# STC89C52.net
KiCad netlist of a schematic drawn in Altium Designer
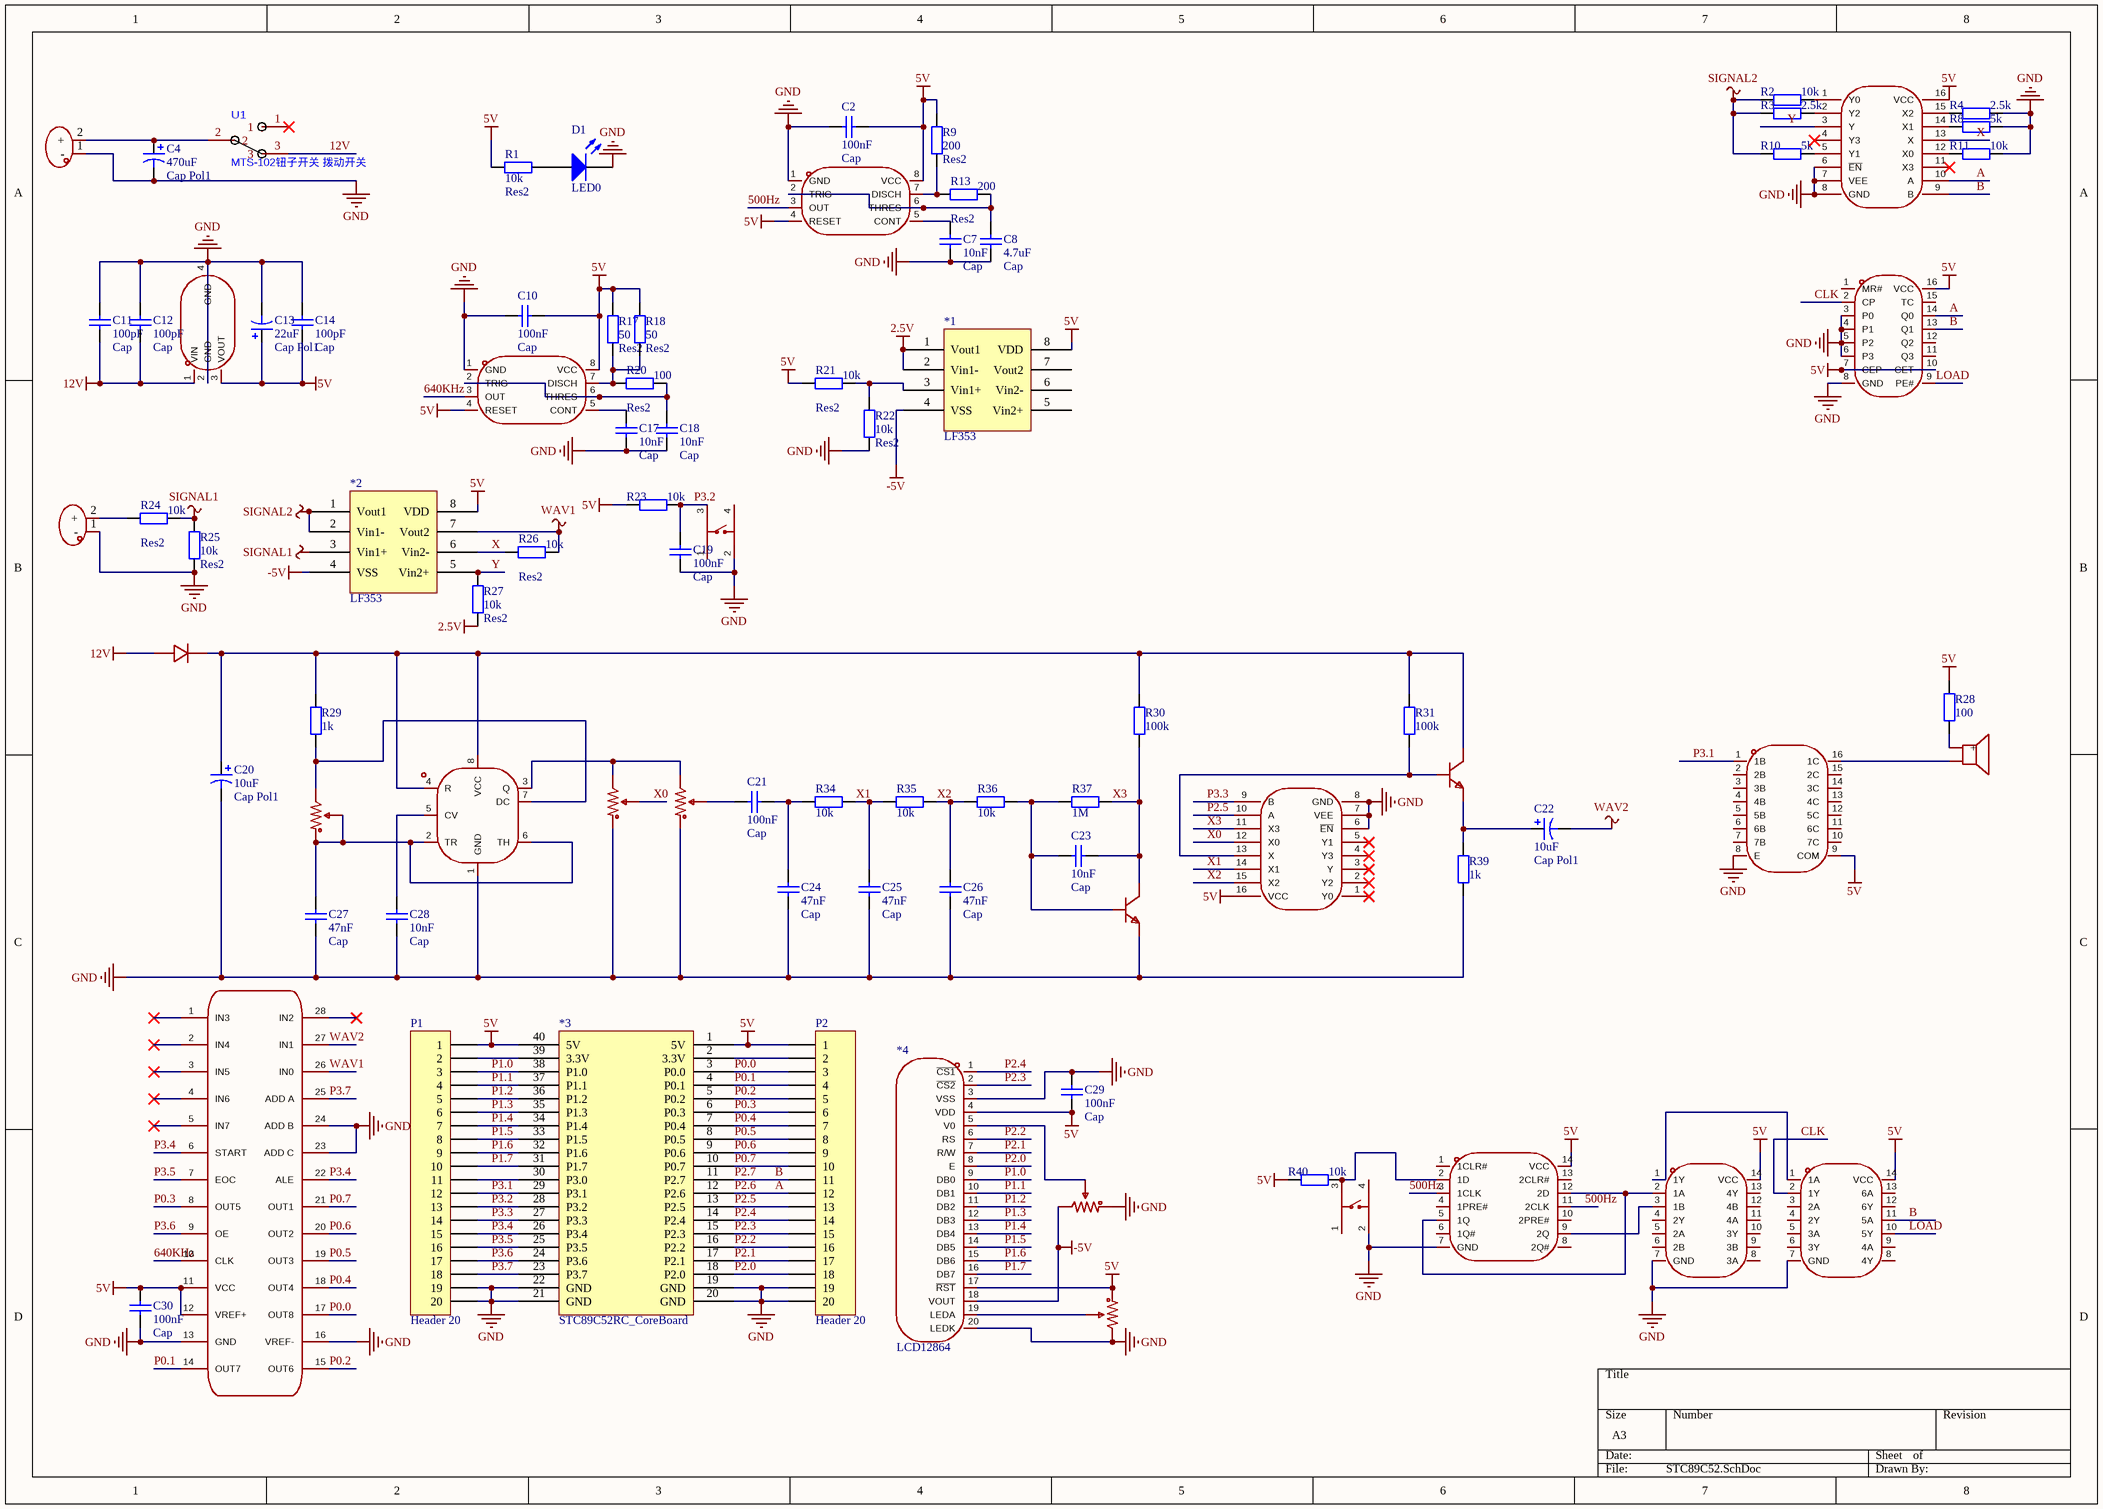
[diagram p0: STC89C52.SchDoc]

(export (version "E")
  (design (tool "Eeschema 10.0.6"))
  (components
    (comp (ref "*1") (value "LF353") (footprint "MCP6022") (libsource (lib "STC89C52") (part "MCP6022")))
    (comp (ref "*2") (value "LF353") (footprint "MCP6022") (libsource (lib "STC89C52") (part "MCP6022")))
    (comp (ref "*3")
      (value "STC89C52RC_CoreBoard")
      (footprint "STC89C52RC_CoreBoard")
      (libsource (lib "STC89C52") (part "STC89C52RC_CoreBoard"))
    )
    (comp (ref "*4") (value "LCD12864") (footprint "LCD12864") (libsource (lib "STC89C52") (part "LCD12864")))
    (comp (ref "BUZZER1")
      (value "2.7kHz")
      (footprint "BEEP 5x9x5.5")
      (fields (field (name "MANUFACTURER") "华能") (field (name "MANUFACTURER PART") "TMB12A05"))
      (libsource (lib "缩微光电核心板（CYT2BL3）") (part "蜂鸣器"))
    )
    (comp (ref "C2")
      (value "Cap")
      (footprint "C0603_M")
      (description "Capacitor")
      (fields (field (name "ALTIUM_VALUE") "100nF") (field (name "PUBLISHER") "Altium Limited"))
      (libsource (lib "Miscellaneous Devices") (part "Cap"))
    )
    (comp (ref "C4")
      (value "Cap Pol1")
      (footprint "CAP-SMD_BD8.0-L8.3-W8.3-FD")
      (description "Polarized Capacitor (Radial)")
      (fields (field (name "ALTIUM_VALUE") "470uF") (field (name "PUBLISHER") "Altium Limited"))
      (libsource (lib "Miscellaneous Devices") (part "Cap Pol1"))
    )
    (comp (ref "C7")
      (value "Cap")
      (footprint "C0603_M")
      (description "Capacitor")
      (fields (field (name "ALTIUM_VALUE") "10nF") (field (name "PUBLISHER") "Altium Limited"))
      (libsource (lib "Miscellaneous Devices") (part "Cap"))
    )
    (comp (ref "C8")
      (value "Cap")
      (footprint "C0603_M")
      (description "Capacitor")
      (fields (field (name "ALTIUM_VALUE") "4.7uF") (field (name "PUBLISHER") "Altium Limited"))
      (libsource (lib "Miscellaneous Devices") (part "Cap"))
    )
    (comp (ref "C10")
      (value "Cap")
      (footprint "C0603_M")
      (description "Capacitor")
      (fields (field (name "ALTIUM_VALUE") "100nF") (field (name "PUBLISHER") "Altium Limited"))
      (libsource (lib "Miscellaneous Devices") (part "Cap"))
    )
    (comp (ref "C11")
      (value "Cap")
      (footprint "C0603_M")
      (description "Capacitor")
      (fields (field (name "ALTIUM_VALUE") "100pF") (field (name "PUBLISHER") "Altium Limited"))
      (libsource (lib "Miscellaneous Devices") (part "Cap"))
    )
    (comp (ref "C12")
      (value "Cap")
      (footprint "C0603_M")
      (description "Capacitor")
      (fields (field (name "ALTIUM_VALUE") "100pF") (field (name "PUBLISHER") "Altium Limited"))
      (libsource (lib "Miscellaneous Devices") (part "Cap"))
    )
    (comp (ref "C13")
      (value "Cap Pol1")
      (footprint "C_3528")
      (description "Polarized Capacitor (Radial)")
      (fields (field (name "ALTIUM_VALUE") "22uF") (field (name "PUBLISHER") "Altium Limited"))
      (libsource (lib "Miscellaneous Devices") (part "Cap Pol1"))
    )
    (comp (ref "C14")
      (value "Cap")
      (footprint "C0603_M")
      (description "Capacitor")
      (fields (field (name "ALTIUM_VALUE") "100pF") (field (name "PUBLISHER") "Altium Limited"))
      (libsource (lib "Miscellaneous Devices") (part "Cap"))
    )
    (comp (ref "C17")
      (value "Cap")
      (footprint "C0603_M")
      (description "Capacitor")
      (fields (field (name "ALTIUM_VALUE") "10nF") (field (name "PUBLISHER") "Altium Limited"))
      (libsource (lib "Miscellaneous Devices") (part "Cap"))
    )
    (comp (ref "C18")
      (value "Cap")
      (footprint "C0603_M")
      (description "Capacitor")
      (fields (field (name "ALTIUM_VALUE") "10nF") (field (name "PUBLISHER") "Altium Limited"))
      (libsource (lib "Miscellaneous Devices") (part "Cap"))
    )
    (comp (ref "C19")
      (value "Cap")
      (footprint "C0603_M")
      (description "Capacitor")
      (fields (field (name "ALTIUM_VALUE") "100nF") (field (name "PUBLISHER") "Altium Limited"))
      (libsource (lib "Miscellaneous Devices") (part "Cap"))
    )
    (comp (ref "C20")
      (value "Cap Pol1")
      (footprint "C_3528")
      (description "Polarized Capacitor (Radial)")
      (fields (field (name "ALTIUM_VALUE") "10uF") (field (name "PUBLISHER") "Altium Limited"))
      (libsource (lib "Miscellaneous Devices") (part "Cap Pol1"))
    )
    (comp (ref "C21")
      (value "Cap")
      (footprint "C0603_M")
      (description "Capacitor")
      (fields (field (name "ALTIUM_VALUE") "100nF") (field (name "PUBLISHER") "Altium Limited"))
      (libsource (lib "Miscellaneous Devices") (part "Cap"))
    )
    (comp (ref "C22")
      (value "Cap Pol1")
      (footprint "C_3528")
      (description "Polarized Capacitor (Radial)")
      (fields (field (name "ALTIUM_VALUE") "10uF") (field (name "PUBLISHER") "Altium Limited"))
      (libsource (lib "Miscellaneous Devices") (part "Cap Pol1"))
    )
    (comp (ref "C23")
      (value "Cap")
      (footprint "C0603_M")
      (description "Capacitor")
      (fields (field (name "ALTIUM_VALUE") "10nF") (field (name "PUBLISHER") "Altium Limited"))
      (libsource (lib "Miscellaneous Devices") (part "Cap"))
    )
    (comp (ref "C24")
      (value "Cap")
      (footprint "C0603_M")
      (description "Capacitor")
      (fields (field (name "ALTIUM_VALUE") "47nF") (field (name "PUBLISHER") "Altium Limited"))
      (libsource (lib "Miscellaneous Devices") (part "Cap"))
    )
    (comp (ref "C25")
      (value "Cap")
      (footprint "C0603_M")
      (description "Capacitor")
      (fields (field (name "ALTIUM_VALUE") "47nF") (field (name "PUBLISHER") "Altium Limited"))
      (libsource (lib "Miscellaneous Devices") (part "Cap"))
    )
    (comp (ref "C26")
      (value "Cap")
      (footprint "C0603_M")
      (description "Capacitor")
      (fields (field (name "ALTIUM_VALUE") "47nF") (field (name "PUBLISHER") "Altium Limited"))
      (libsource (lib "Miscellaneous Devices") (part "Cap"))
    )
    (comp (ref "C27")
      (value "Cap")
      (footprint "C0603_M")
      (description "Capacitor")
      (fields (field (name "ALTIUM_VALUE") "47nF") (field (name "PUBLISHER") "Altium Limited"))
      (libsource (lib "Miscellaneous Devices") (part "Cap"))
    )
    (comp (ref "C28")
      (value "Cap")
      (footprint "C0603_M")
      (description "Capacitor")
      (fields (field (name "ALTIUM_VALUE") "10nF") (field (name "PUBLISHER") "Altium Limited"))
      (libsource (lib "Miscellaneous Devices") (part "Cap"))
    )
    (comp (ref "C29")
      (value "Cap")
      (footprint "C0603_M")
      (description "Capacitor")
      (fields (field (name "ALTIUM_VALUE") "100nF") (field (name "PUBLISHER") "Altium Limited"))
      (libsource (lib "Miscellaneous Devices") (part "Cap"))
    )
    (comp (ref "C30")
      (value "Cap")
      (footprint "C0603_M")
      (description "Capacitor")
      (fields (field (name "ALTIUM_VALUE") "100nF") (field (name "PUBLISHER") "Altium Limited"))
      (libsource (lib "Miscellaneous Devices") (part "Cap"))
    )
    (comp (ref "D1")
      (value "LED0")
      (footprint "LED0805_W")
      (description "Typical INFRARED GaAs LED")
      (fields (field (name "PUBLISHER") "Altium Limited"))
      (libsource (lib "Miscellaneous Devices") (part "LED0"))
    )
    (comp (ref "D4")
      (value "1N4007W_C18199088")
      (footprint "1N4007")
      (libsource (lib "STC89C52") (part "1N4007W_C18199088"))
    )
    (comp (ref "P1")
      (value "Header 20")
      (footprint "HDR1X20")
      (description "Header, 20-Pin")
      (fields (field (name "PUBLISHER") "Altium Limited"))
      (libsource (lib "Miscellaneous Connectors") (part "Header 20"))
    )
    (comp (ref "P2")
      (value "Header 20")
      (footprint "HDR1X20")
      (description "Header, 20-Pin")
      (fields (field (name "PUBLISHER") "Altium Limited"))
      (libsource (lib "") (part "Header 20_1"))
    )
    (comp (ref "Q3")
      (value "MMS8050-H-TP")
      (footprint "S8050")
      (libsource (lib "STC89C52") (part "MMS8050-H-TP"))
    )
    (comp (ref "Q4")
      (value "MMS8050-H-TP")
      (footprint "S8050")
      (libsource (lib "STC89C52") (part "MMS8050-H-TP"))
    )
    (comp (ref "R1")
      (value "Res2")
      (footprint "R0603_M")
      (description "Resistor")
      (fields (field (name "ALTIUM_VALUE") "10k") (field (name "PUBLISHER") "Altium Limited"))
      (libsource (lib "") (part "Res2_2"))
    )
    (comp (ref "R2")
      (value "10k")
      (footprint "R0603_M")
      (description "Resistor")
      (fields (field (name "Comment") "Res2") (field (name "PUBLISHER") "Altium Limited"))
      (libsource (lib "Miscellaneous Devices") (part "Res2"))
    )
    (comp (ref "R3")
      (value "2.5k")
      (footprint "R0603_M")
      (description "Resistor")
      (fields (field (name "Comment") "Res2") (field (name "PUBLISHER") "Altium Limited"))
      (libsource (lib "Miscellaneous Devices") (part "Res2"))
    )
    (comp (ref "R4")
      (value "2.5k")
      (footprint "R0603_M")
      (description "Resistor")
      (fields (field (name "Comment") "Res2") (field (name "PUBLISHER") "Altium Limited"))
      (libsource (lib "Miscellaneous Devices") (part "Res2"))
    )
    (comp (ref "R8")
      (value "5k")
      (footprint "R0603_M")
      (description "Resistor")
      (fields (field (name "Comment") "Res2") (field (name "PUBLISHER") "Altium Limited"))
      (libsource (lib "Miscellaneous Devices") (part "Res2"))
    )
    (comp (ref "R9")
      (value "Res2")
      (footprint "R0603_M")
      (description "Resistor")
      (fields (field (name "ALTIUM_VALUE") "200") (field (name "PUBLISHER") "Altium Limited"))
      (libsource (lib "") (part "Res2_3"))
    )
    (comp (ref "R10")
      (value "5k")
      (footprint "R0603_M")
      (description "Resistor")
      (fields (field (name "Comment") "Res2") (field (name "PUBLISHER") "Altium Limited"))
      (libsource (lib "Miscellaneous Devices") (part "Res2"))
    )
    (comp (ref "R11")
      (value "10k")
      (footprint "R0603_M")
      (description "Resistor")
      (fields (field (name "Comment") "Res2") (field (name "PUBLISHER") "Altium Limited"))
      (libsource (lib "Miscellaneous Devices") (part "Res2"))
    )
    (comp (ref "R13")
      (value "Res2")
      (footprint "R0603_M")
      (description "Resistor")
      (fields (field (name "ALTIUM_VALUE") "200") (field (name "PUBLISHER") "Altium Limited"))
      (libsource (lib "Miscellaneous Devices") (part "Res2"))
    )
    (comp (ref "R17")
      (value "Res2")
      (footprint "R0603_M")
      (description "Resistor")
      (fields (field (name "ALTIUM_VALUE") "50") (field (name "PUBLISHER") "Altium Limited"))
      (libsource (lib "") (part "Res2_3"))
    )
    (comp (ref "R18")
      (value "Res2")
      (footprint "R0603_M")
      (description "Resistor")
      (fields (field (name "ALTIUM_VALUE") "50") (field (name "PUBLISHER") "Altium Limited"))
      (libsource (lib "") (part "Res2_3"))
    )
    (comp (ref "R20")
      (value "Res2")
      (footprint "R0603_M")
      (description "Resistor")
      (fields (field (name "ALTIUM_VALUE") "100") (field (name "PUBLISHER") "Altium Limited"))
      (libsource (lib "Miscellaneous Devices") (part "Res2"))
    )
    (comp (ref "R21")
      (value "Res2")
      (footprint "R0603_M")
      (description "Resistor")
      (fields (field (name "ALTIUM_VALUE") "10k") (field (name "PUBLISHER") "Altium Limited"))
      (libsource (lib "Miscellaneous Devices") (part "Res2"))
    )
    (comp (ref "R22")
      (value "Res2")
      (footprint "R0603_M")
      (description "Resistor")
      (fields (field (name "ALTIUM_VALUE") "10k") (field (name "PUBLISHER") "Altium Limited"))
      (libsource (lib "") (part "Res2_1"))
    )
    (comp (ref "R23")
      (value "10k")
      (footprint "R0603_M")
      (description "Resistor")
      (fields (field (name "Comment") "Res2") (field (name "PUBLISHER") "Altium Limited"))
      (libsource (lib "Miscellaneous Devices") (part "Res2"))
    )
    (comp (ref "R24")
      (value "Res2")
      (footprint "R0603_M")
      (description "Resistor")
      (fields (field (name "ALTIUM_VALUE") "10k") (field (name "PUBLISHER") "Altium Limited"))
      (libsource (lib "Miscellaneous Devices") (part "Res2"))
    )
    (comp (ref "R25")
      (value "Res2")
      (footprint "R0603_M")
      (description "Resistor")
      (fields (field (name "ALTIUM_VALUE") "10k") (field (name "PUBLISHER") "Altium Limited"))
      (libsource (lib "") (part "Res2_1"))
    )
    (comp (ref "R26")
      (value "Res2")
      (footprint "R0603_M")
      (description "Resistor")
      (fields (field (name "ALTIUM_VALUE") "10k") (field (name "PUBLISHER") "Altium Limited"))
      (libsource (lib "Miscellaneous Devices") (part "Res2"))
    )
    (comp (ref "R27")
      (value "Res2")
      (footprint "R0603_M")
      (description "Resistor")
      (fields (field (name "ALTIUM_VALUE") "10k") (field (name "PUBLISHER") "Altium Limited"))
      (libsource (lib "") (part "Res2_1"))
    )
    (comp (ref "R28")
      (value "100")
      (footprint "R0603_M")
      (description "Resistor")
      (fields (field (name "Comment") "Res2") (field (name "PUBLISHER") "Altium Limited"))
      (libsource (lib "") (part "Res2_1"))
    )
    (comp (ref "R29")
      (value "1k")
      (footprint "R0603_M")
      (description "Resistor")
      (fields (field (name "Comment") "Res2") (field (name "PUBLISHER") "Altium Limited"))
      (libsource (lib "") (part "Res2_3"))
    )
    (comp (ref "R30")
      (value "100k")
      (footprint "R0603_M")
      (description "Resistor")
      (fields (field (name "Comment") "Res2") (field (name "PUBLISHER") "Altium Limited"))
      (libsource (lib "") (part "Res2_1"))
    )
    (comp (ref "R31")
      (value "100k")
      (footprint "R0603_M")
      (description "Resistor")
      (fields (field (name "Comment") "Res2") (field (name "PUBLISHER") "Altium Limited"))
      (libsource (lib "") (part "Res2_1"))
    )
    (comp (ref "R32")
      (value "3362P-1-203_C48997909")
      (footprint "RES-ADJ-TH_3362P")
      (libsource (lib "STC89C52") (part "3362P-1-203_C48997909"))
    )
    (comp (ref "R33")
      (value "3362P-1-203_C48997909")
      (footprint "RES-ADJ-TH_3362P")
      (libsource (lib "STC89C52") (part "3362P-1-203_C48997909"))
    )
    (comp (ref "R34")
      (value "10k")
      (footprint "R0603_M")
      (description "Resistor")
      (fields (field (name "Comment") "Res2") (field (name "PUBLISHER") "Altium Limited"))
      (libsource (lib "") (part "Res2_2"))
    )
    (comp (ref "R35")
      (value "10k")
      (footprint "R0603_M")
      (description "Resistor")
      (fields (field (name "Comment") "Res2") (field (name "PUBLISHER") "Altium Limited"))
      (libsource (lib "") (part "Res2_2"))
    )
    (comp (ref "R36")
      (value "10k")
      (footprint "R0603_M")
      (description "Resistor")
      (fields (field (name "Comment") "Res2") (field (name "PUBLISHER") "Altium Limited"))
      (libsource (lib "") (part "Res2_2"))
    )
    (comp (ref "R37")
      (value "1M")
      (footprint "R0603_M")
      (description "Resistor")
      (fields (field (name "Comment") "Res2") (field (name "PUBLISHER") "Altium Limited"))
      (libsource (lib "") (part "Res2_2"))
    )
    (comp (ref "R38")
      (value "3362P-1-203_C48997909")
      (footprint "RES-ADJ-TH_3362P")
      (libsource (lib "STC89C52") (part "3362P-1-203_C48997909"))
    )
    (comp (ref "R39")
      (value "1k")
      (footprint "R0603_M")
      (description "Resistor")
      (fields (field (name "Comment") "Res2") (field (name "PUBLISHER") "Altium Limited"))
      (libsource (lib "") (part "Res2_1"))
    )
    (comp (ref "R40")
      (value "10k")
      (footprint "R0603_M")
      (description "Resistor")
      (fields (field (name "Comment") "Res2") (field (name "PUBLISHER") "Altium Limited"))
      (libsource (lib "Miscellaneous Devices") (part "Res2"))
    )
    (comp (ref "R41")
      (value "3362P-1-203_C48997909")
      (footprint "RES-ADJ-TH_3362P")
      (libsource (lib "STC89C52") (part "3362P-1-203_C48997909"))
    )
    (comp (ref "R42")
      (value "3362P-1-203_C48997909")
      (footprint "RES-ADJ-TH_3362P")
      (libsource (lib "STC89C52") (part "3362P-1-203_C48997909"))
    )
    (comp (ref "SW1")
      (value "KH-6X6X8H-STM")
      (footprint "SW-SMD_4P-L6.0-W6.0-P4.50-LS9.0-1")
      (libsource (lib "STC89C52") (part "KH-6X6X8H-STM"))
    )
    (comp (ref "SW2")
      (value "KH-6X6X8H-STM")
      (footprint "SW-SMD_4P-L6.0-W6.0-P4.50-LS9.0-1")
      (libsource (lib "STC89C52") (part "KH-6X6X8H-STM"))
    )
    (comp (ref "U1")
      (value "MTS-102钮子开关 拨动开关")
      (footprint "MTS102")
      (libsource (lib "缩微光电核心板（CYT2BL3）") (part "MTS-102钮子开关 拨动开关"))
    )
    (comp (ref "U2")
      (value "XT30U-F")
      (footprint "CONN-TH_XT60")
      (fields (field (name "MANUFACTURER") "AMASS(艾迈斯)"))
      (libsource (lib "缩微光电核心板（CYT2BL3）") (part "XT30U-F"))
    )
    (comp (ref "U3")
      (value "74HC4052PW,118")
      (footprint "74HC4052")
      (libsource (lib "STC89C52") (part "74HC4052PW,118"))
    )
    (comp (ref "U5")
      (value "NE555DR_C695838")
      (footprint "NE555")
      (libsource (lib "STC89C52") (part "NE555DR_C695838"))
    )
    (comp (ref "U6")
      (value "LM2940S-5.0/TR")
      (footprint "LM2940")
      (libsource (lib "缩微光电核心板（CYT2BL3）") (part "LM2940S-5.0/TR"))
    )
    (comp (ref "U7")
      (value "SN74LS161ADR(LX)")
      (footprint "74LS161")
      (libsource (lib "STC89C52") (part "SN74LS161ADR(LX)"))
    )
    (comp (ref "U8")
      (value "NE555DR_C695838")
      (footprint "NE555")
      (libsource (lib "STC89C52") (part "NE555DR_C695838"))
    )
    (comp (ref "U9")
      (value "XT30U-F")
      (footprint "HDR1X2")
      (fields (field (name "MANUFACTURER") "AMASS(艾迈斯)"))
      (libsource (lib "缩微光电核心板（CYT2BL3）") (part "XT30U-F"))
    )
    (comp (ref "U10")
      (value "NE555DR_C695838")
      (footprint "NE555")
      (libsource (lib "STC89C52") (part "NE555"))
    )
    (comp (ref "U11")
      (value "ULN2003D1013TR")
      (footprint "ULN2003D")
      (libsource (lib "STC89C52") (part "ULN2003D1013TR_1"))
    )
    (comp (ref "U12")
      (value "74HC4052PW,118")
      (footprint "74HC4052")
      (libsource (lib "STC89C52") (part "74HC4052PW,118"))
    )
    (comp (ref "U13")
      (value "SN74LS74ADR")
      (footprint "74LS74")
      (libsource (lib "STC89C52") (part "SN74LS74ADR"))
    )
    (comp (ref "U14")
      (value "SN74HC02N")
      (footprint "74HC02")
      (libsource (lib "STC89C52") (part "SN74HC02N"))
    )
    (comp (ref "U15")
      (value "SN74HC04DR")
      (footprint "74HC04")
      (libsource (lib "STC89C52") (part "SN74HC04DR"))
    )
    (comp (ref "U16")
      (value "DS1009-28AT1WX-0A2")
      (footprint "ADC0808")
      (libsource (lib "STC89C52") (part "ADC0808"))
    )
  )
  (nets
    (net (code "1") (name "-5V") (class "Default")
      (node (ref "*1") (pin "4") (pinfunction "VSS_4") (pintype "passive"))
      (node (ref "*2") (pin "4") (pinfunction "VSS_4") (pintype "passive"))
      (node (ref "*4") (pin "18") (pinfunction "VOUT_18") (pintype "passive"))
      (node (ref "R42") (pin "3") (pinfunction "3_3") (pintype "passive"))
    )
    (net (code "2") (name "/500Hz") (class "Default")
      (node (ref "U13") (pin "11") (pinfunction "2CLK_11") (pintype "passive"))
      (node (ref "U13") (pin "3") (pinfunction "1CLK_3") (pintype "passive"))
      (node (ref "U5") (pin "3") (pinfunction "OUT_3") (pintype "passive"))
    )
    (net (code "3") (name "/640KHz") (class "Default")
      (node (ref "U16") (pin "10") (pinfunction "CLK_10") (pintype "passive"))
      (node (ref "U8") (pin "3") (pinfunction "OUT_3") (pintype "passive"))
    )
    (net (code "4") (name "/A") (class "Default")
      (node (ref "*3") (pin "12") (pinfunction "P2.6_12") (pintype "passive"))
      (node (ref "P2") (pin "12") (pinfunction "12_12") (pintype "passive"))
      (node (ref "U3") (pin "10") (pinfunction "A_10") (pintype "passive"))
      (node (ref "U7") (pin "14") (pinfunction "Q0_14") (pintype "passive"))
    )
    (net (code "5") (name "/B") (class "Default")
      (node (ref "*3") (pin "11") (pinfunction "P2.7_11") (pintype "passive"))
      (node (ref "P2") (pin "11") (pinfunction "11_11") (pintype "passive"))
      (node (ref "U15") (pin "11") (pinfunction "5A_11") (pintype "passive"))
      (node (ref "U3") (pin "9") (pinfunction "B_9") (pintype "passive"))
      (node (ref "U7") (pin "13") (pinfunction "Q1_13") (pintype "passive"))
    )
    (net (code "6") (name "/CLK") (class "Default")
      (node (ref "U15") (pin "2") (pinfunction "1Y_2") (pintype "passive"))
      (node (ref "U7") (pin "2") (pinfunction "CP_2") (pintype "passive"))
    )
    (net (code "7") (name "/LOAD") (class "Default")
      (node (ref "U15") (pin "10") (pinfunction "5Y_10") (pintype "passive"))
      (node (ref "U7") (pin "9") (pinfunction "PE#_9") (pintype "passive"))
    )
    (net (code "8") (name "/P0.0") (class "Default")
      (node (ref "*3") (pin "3") (pinfunction "P0.0_3") (pintype "passive"))
      (node (ref "P2") (pin "3") (pinfunction "3_3") (pintype "passive"))
      (node (ref "U16") (pin "17") (pinfunction "OUT8_17") (pintype "passive"))
    )
    (net (code "9") (name "/P0.1") (class "Default")
      (node (ref "*3") (pin "4") (pinfunction "P0.1_4") (pintype "passive"))
      (node (ref "P2") (pin "4") (pinfunction "4_4") (pintype "passive"))
      (node (ref "U16") (pin "14") (pinfunction "OUT7_14") (pintype "passive"))
    )
    (net (code "10") (name "/P0.2") (class "Default")
      (node (ref "*3") (pin "5") (pinfunction "P0.2_5") (pintype "passive"))
      (node (ref "P2") (pin "5") (pinfunction "5_5") (pintype "passive"))
      (node (ref "U16") (pin "15") (pinfunction "OUT6_15") (pintype "passive"))
    )
    (net (code "11") (name "/P0.3") (class "Default")
      (node (ref "*3") (pin "6") (pinfunction "P0.3_6") (pintype "passive"))
      (node (ref "P2") (pin "6") (pinfunction "6_6") (pintype "passive"))
      (node (ref "U16") (pin "8") (pinfunction "OUT5_8") (pintype "passive"))
    )
    (net (code "12") (name "/P0.4") (class "Default")
      (node (ref "*3") (pin "7") (pinfunction "P0.4_7") (pintype "passive"))
      (node (ref "P2") (pin "7") (pinfunction "7_7") (pintype "passive"))
      (node (ref "U16") (pin "18") (pinfunction "OUT4_18") (pintype "passive"))
    )
    (net (code "13") (name "/P0.5") (class "Default")
      (node (ref "*3") (pin "8") (pinfunction "P0.5_8") (pintype "passive"))
      (node (ref "P2") (pin "8") (pinfunction "8_8") (pintype "passive"))
      (node (ref "U16") (pin "19") (pinfunction "OUT3_19") (pintype "passive"))
    )
    (net (code "14") (name "/P0.6") (class "Default")
      (node (ref "*3") (pin "9") (pinfunction "P0.6_9") (pintype "passive"))
      (node (ref "P2") (pin "9") (pinfunction "9_9") (pintype "passive"))
      (node (ref "U16") (pin "20") (pinfunction "OUT2_20") (pintype "passive"))
    )
    (net (code "15") (name "/P0.7") (class "Default")
      (node (ref "*3") (pin "10") (pinfunction "P0.7_10") (pintype "passive"))
      (node (ref "P2") (pin "10") (pinfunction "10_10") (pintype "passive"))
      (node (ref "U16") (pin "21") (pinfunction "OUT1_21") (pintype "passive"))
    )
    (net (code "16") (name "/P1.0") (class "Default")
      (node (ref "*3") (pin "38") (pinfunction "P1.0_38") (pintype "passive"))
      (node (ref "*4") (pin "9") (pinfunction "DB0_9") (pintype "passive"))
      (node (ref "P1") (pin "3") (pinfunction "3_3") (pintype "passive"))
    )
    (net (code "17") (name "/P1.1") (class "Default")
      (node (ref "*3") (pin "37") (pinfunction "P1.1_37") (pintype "passive"))
      (node (ref "*4") (pin "10") (pinfunction "DB1_10") (pintype "passive"))
      (node (ref "P1") (pin "4") (pinfunction "4_4") (pintype "passive"))
    )
    (net (code "18") (name "/P1.2") (class "Default")
      (node (ref "*3") (pin "36") (pinfunction "P1.2_36") (pintype "passive"))
      (node (ref "*4") (pin "11") (pinfunction "DB2_11") (pintype "passive"))
      (node (ref "P1") (pin "5") (pinfunction "5_5") (pintype "passive"))
    )
    (net (code "19") (name "/P1.3") (class "Default")
      (node (ref "*3") (pin "35") (pinfunction "P1.3_35") (pintype "passive"))
      (node (ref "*4") (pin "12") (pinfunction "DB3_12") (pintype "passive"))
      (node (ref "P1") (pin "6") (pinfunction "6_6") (pintype "passive"))
    )
    (net (code "20") (name "/P1.4") (class "Default")
      (node (ref "*3") (pin "34") (pinfunction "P1.4_34") (pintype "passive"))
      (node (ref "*4") (pin "13") (pinfunction "DB4_13") (pintype "passive"))
      (node (ref "P1") (pin "7") (pinfunction "7_7") (pintype "passive"))
    )
    (net (code "21") (name "/P1.5") (class "Default")
      (node (ref "*3") (pin "33") (pinfunction "P1.5_33") (pintype "passive"))
      (node (ref "*4") (pin "14") (pinfunction "DB5_14") (pintype "passive"))
      (node (ref "P1") (pin "8") (pinfunction "8_8") (pintype "passive"))
    )
    (net (code "22") (name "/P1.6") (class "Default")
      (node (ref "*3") (pin "32") (pinfunction "P1.6_32") (pintype "passive"))
      (node (ref "*4") (pin "15") (pinfunction "DB6_15") (pintype "passive"))
      (node (ref "P1") (pin "9") (pinfunction "9_9") (pintype "passive"))
    )
    (net (code "23") (name "/P1.7") (class "Default")
      (node (ref "*3") (pin "31") (pinfunction "P1.7_31") (pintype "passive"))
      (node (ref "*4") (pin "16") (pinfunction "DB7_16") (pintype "passive"))
      (node (ref "P1") (pin "10") (pinfunction "10_10") (pintype "passive"))
    )
    (net (code "24") (name "/P2.0") (class "Default")
      (node (ref "*3") (pin "18") (pinfunction "P2.0_18") (pintype "passive"))
      (node (ref "*4") (pin "8") (pinfunction "E_8") (pintype "passive"))
      (node (ref "P2") (pin "18") (pinfunction "18_18") (pintype "passive"))
    )
    (net (code "25") (name "/P2.1") (class "Default")
      (node (ref "*3") (pin "17") (pinfunction "P2.1_17") (pintype "passive"))
      (node (ref "*4") (pin "7") (pinfunction "R/W_7") (pintype "passive"))
      (node (ref "P2") (pin "17") (pinfunction "17_17") (pintype "passive"))
    )
    (net (code "26") (name "/P2.2") (class "Default")
      (node (ref "*3") (pin "16") (pinfunction "P2.2_16") (pintype "passive"))
      (node (ref "*4") (pin "6") (pinfunction "RS_6") (pintype "passive"))
      (node (ref "P2") (pin "16") (pinfunction "16_16") (pintype "passive"))
    )
    (net (code "27") (name "/P2.3") (class "Default")
      (node (ref "*3") (pin "15") (pinfunction "P2.3_15") (pintype "passive"))
      (node (ref "*4") (pin "2") (pinfunction "~{CS2}_2") (pintype "passive"))
      (node (ref "P2") (pin "15") (pinfunction "15_15") (pintype "passive"))
    )
    (net (code "28") (name "/P2.4") (class "Default")
      (node (ref "*3") (pin "14") (pinfunction "P2.4_14") (pintype "passive"))
      (node (ref "*4") (pin "1") (pinfunction "~{CS1}_1") (pintype "passive"))
      (node (ref "P2") (pin "14") (pinfunction "14_14") (pintype "passive"))
    )
    (net (code "29") (name "/P2.5") (class "Default")
      (node (ref "*3") (pin "13") (pinfunction "P2.5_13") (pintype "passive"))
      (node (ref "P2") (pin "13") (pinfunction "13_13") (pintype "passive"))
      (node (ref "U12") (pin "10") (pinfunction "A_10") (pintype "passive"))
    )
    (net (code "30") (name "/P3.1") (class "Default")
      (node (ref "*3") (pin "29") (pinfunction "P3.1_29") (pintype "passive"))
      (node (ref "P1") (pin "12") (pinfunction "12_12") (pintype "passive"))
      (node (ref "U11") (pin "1") (pinfunction "1B_1") (pintype "passive"))
    )
    (net (code "31") (name "/P3.2") (class "Default")
      (node (ref "*3") (pin "28") (pinfunction "P3.2_28") (pintype "passive"))
      (node (ref "C19") (pin "1") (pinfunction "1_1") (pintype "passive"))
      (node (ref "P1") (pin "13") (pinfunction "13_13") (pintype "passive"))
      (node (ref "R23") (pin "2") (pinfunction "2_2") (pintype "passive"))
      (node (ref "SW1") (pin "3") (pinfunction "B_3") (pintype "passive"))
    )
    (net (code "32") (name "/P3.3") (class "Default")
      (node (ref "*3") (pin "27") (pinfunction "P3.3_27") (pintype "passive"))
      (node (ref "P1") (pin "14") (pinfunction "14_14") (pintype "passive"))
      (node (ref "U12") (pin "9") (pinfunction "B_9") (pintype "passive"))
    )
    (net (code "33") (name "/P3.4") (class "Default")
      (node (ref "*3") (pin "26") (pinfunction "P3.4_26") (pintype "passive"))
      (node (ref "P1") (pin "15") (pinfunction "15_15") (pintype "passive"))
      (node (ref "U16") (pin "22") (pinfunction "ALE_22") (pintype "passive"))
      (node (ref "U16") (pin "6") (pinfunction "START_6") (pintype "passive"))
    )
    (net (code "34") (name "/P3.5") (class "Default")
      (node (ref "*3") (pin "25") (pinfunction "P3.5_25") (pintype "passive"))
      (node (ref "P1") (pin "16") (pinfunction "16_16") (pintype "passive"))
      (node (ref "U16") (pin "7") (pinfunction "EOC_7") (pintype "passive"))
    )
    (net (code "35") (name "/P3.6") (class "Default")
      (node (ref "*3") (pin "24") (pinfunction "P3.6_24") (pintype "passive"))
      (node (ref "P1") (pin "17") (pinfunction "17_17") (pintype "passive"))
      (node (ref "U16") (pin "9") (pinfunction "OE_9") (pintype "passive"))
    )
    (net (code "36") (name "/P3.7") (class "Default")
      (node (ref "*3") (pin "23") (pinfunction "P3.7_23") (pintype "passive"))
      (node (ref "P1") (pin "18") (pinfunction "18_18") (pintype "passive"))
      (node (ref "U16") (pin "25") (pinfunction "ADD_A_25") (pintype "passive"))
    )
    (net (code "37") (name "/X") (class "Default")
      (node (ref "*2") (pin "6") (pinfunction "Vin2-_6") (pintype "passive"))
      (node (ref "R26") (pin "1") (pinfunction "1_1") (pintype "passive"))
      (node (ref "U3") (pin "13") (pinfunction "X_13") (pintype "passive"))
    )
    (net (code "38") (name "/X0") (class "Default")
      (node (ref "R32") (pin "2") (pinfunction "2_2") (pintype "passive"))
      (node (ref "U12") (pin "12") (pinfunction "X0_12") (pintype "passive"))
    )
    (net (code "39") (name "/X1") (class "Default")
      (node (ref "C25") (pin "1") (pinfunction "1_1") (pintype "passive"))
      (node (ref "R34") (pin "1") (pinfunction "1_1") (pintype "passive"))
      (node (ref "R35") (pin "2") (pinfunction "2_2") (pintype "passive"))
      (node (ref "U12") (pin "14") (pinfunction "X1_14") (pintype "passive"))
    )
    (net (code "40") (name "/X2") (class "Default")
      (node (ref "C26") (pin "1") (pinfunction "1_1") (pintype "passive"))
      (node (ref "R35") (pin "1") (pinfunction "1_1") (pintype "passive"))
      (node (ref "R36") (pin "2") (pinfunction "2_2") (pintype "passive"))
      (node (ref "U12") (pin "15") (pinfunction "X2_15") (pintype "passive"))
    )
    (net (code "41") (name "/X3") (class "Default")
      (node (ref "C23") (pin "2") (pinfunction "2_2") (pintype "passive"))
      (node (ref "Q4") (pin "3") (pinfunction "C_3") (pintype "passive"))
      (node (ref "R30") (pin "2") (pinfunction "2_2") (pintype "passive"))
      (node (ref "R37") (pin "1") (pinfunction "1_1") (pintype "passive"))
      (node (ref "U12") (pin "11") (pinfunction "X3_11") (pintype "passive"))
    )
    (net (code "42") (name "/Y") (class "Default")
      (node (ref "*2") (pin "5") (pinfunction "Vin2+_5") (pintype "passive"))
      (node (ref "R27") (pin "1") (pinfunction "1_1") (pintype "passive"))
      (node (ref "U3") (pin "3") (pinfunction "Y_3") (pintype "passive"))
    )
    (net (code "43") (name "2.5V") (class "Default")
      (node (ref "*1") (pin "1") (pinfunction "Vout1_1") (pintype "passive"))
      (node (ref "*1") (pin "2") (pinfunction "Vin1-_2") (pintype "passive"))
      (node (ref "R27") (pin "2") (pinfunction "2_2") (pintype "passive"))
    )
    (net (code "44") (name "5V") (class "Default")
      (node (ref "*1") (pin "8") (pinfunction "VDD_8") (pintype "passive"))
      (node (ref "*2") (pin "8") (pinfunction "VDD_8") (pintype "passive"))
      (node (ref "*3") (pin "1") (pinfunction "5V_1") (pintype "passive"))
      (node (ref "*3") (pin "40") (pinfunction "5V_40") (pintype "passive"))
      (node (ref "*4") (pin "17") (pinfunction "~{RST}_17") (pintype "passive"))
      (node (ref "*4") (pin "4") (pinfunction "VDD_4") (pintype "passive"))
      (node (ref "C10") (pin "2") (pinfunction "2_2") (pintype "passive"))
      (node (ref "C13") (pin "1") (pinfunction "1_1") (pintype "passive"))
      (node (ref "C14") (pin "1") (pinfunction "1_1") (pintype "passive"))
      (node (ref "C2") (pin "2") (pinfunction "2_2") (pintype "passive"))
      (node (ref "C29") (pin "1") (pinfunction "1_1") (pintype "passive"))
      (node (ref "C30") (pin "2") (pinfunction "2_2") (pintype "passive"))
      (node (ref "P1") (pin "1") (pinfunction "1_1") (pintype "passive"))
      (node (ref "P2") (pin "1") (pinfunction "1_1") (pintype "passive"))
      (node (ref "R1") (pin "2") (pinfunction "2_2") (pintype "passive"))
      (node (ref "R17") (pin "2") (pinfunction "2_2") (pintype "passive"))
      (node (ref "R18") (pin "2") (pinfunction "2_2") (pintype "passive"))
      (node (ref "R21") (pin "1") (pinfunction "1_1") (pintype "passive"))
      (node (ref "R23") (pin "1") (pinfunction "1_1") (pintype "passive"))
      (node (ref "R28") (pin "1") (pinfunction "1_1") (pintype "passive"))
      (node (ref "R40") (pin "1") (pinfunction "1_1") (pintype "passive"))
      (node (ref "R41") (pin "1") (pinfunction "1_1") (pintype "passive"))
      (node (ref "R9") (pin "2") (pinfunction "2_2") (pintype "passive"))
      (node (ref "U11") (pin "9") (pinfunction "COM_9") (pintype "passive"))
      (node (ref "U12") (pin "16") (pinfunction "VCC_16") (pintype "passive"))
      (node (ref "U13") (pin "14") (pinfunction "VCC_14") (pintype "passive"))
      (node (ref "U14") (pin "14") (pinfunction "VCC_14") (pintype "passive"))
      (node (ref "U15") (pin "14") (pinfunction "VCC_14") (pintype "passive"))
      (node (ref "U16") (pin "11") (pinfunction "VCC_11") (pintype "passive"))
      (node (ref "U16") (pin "12") (pinfunction "VREF+_12") (pintype "passive"))
      (node (ref "U3") (pin "16") (pinfunction "VCC_16") (pintype "passive"))
      (node (ref "U5") (pin "4") (pinfunction "RESET_4") (pintype "passive"))
      (node (ref "U5") (pin "8") (pinfunction "VCC_8") (pintype "passive"))
      (node (ref "U6") (pin "3") (pinfunction "VOUT_3") (pintype "passive"))
      (node (ref "U7") (pin "10") (pinfunction "CET_10") (pintype "passive"))
      (node (ref "U7") (pin "16") (pinfunction "VCC_16") (pintype "passive"))
      (node (ref "U7") (pin "7") (pinfunction "CEP_7") (pintype "passive"))
      (node (ref "U8") (pin "4") (pinfunction "RESET_4") (pintype "passive"))
      (node (ref "U8") (pin "8") (pinfunction "VCC_8") (pintype "passive"))
    )
    (net (code "45") (name "12V") (class "Default")
      (node (ref "C11") (pin "1") (pinfunction "1_1") (pintype "passive"))
      (node (ref "C12") (pin "1") (pinfunction "1_1") (pintype "passive"))
      (node (ref "D4") (pin "2") (pinfunction "A_2") (pintype "passive"))
      (node (ref "U1") (pin "3") (pinfunction "3_3") (pintype "passive"))
      (node (ref "U6") (pin "1") (pinfunction "VIN_1") (pintype "passive"))
    )
    (net (code "46") (name "GND") (class "Default")
      (node (ref "*3") (pin "19") (pinfunction "GND_19") (pintype "passive"))
      (node (ref "*3") (pin "20") (pinfunction "GND_20") (pintype "passive"))
      (node (ref "*3") (pin "21") (pinfunction "GND_21") (pintype "passive"))
      (node (ref "*3") (pin "22") (pinfunction "GND_22") (pintype "passive"))
      (node (ref "*4") (pin "20") (pinfunction "LEDK_20") (pintype "passive"))
      (node (ref "*4") (pin "3") (pinfunction "VSS_3") (pintype "passive"))
      (node (ref "C10") (pin "1") (pinfunction "1_1") (pintype "passive"))
      (node (ref "C11") (pin "2") (pinfunction "2_2") (pintype "passive"))
      (node (ref "C12") (pin "2") (pinfunction "2_2") (pintype "passive"))
      (node (ref "C13") (pin "2") (pinfunction "2_2") (pintype "passive"))
      (node (ref "C14") (pin "2") (pinfunction "2_2") (pintype "passive"))
      (node (ref "C17") (pin "1") (pinfunction "1_1") (pintype "passive"))
      (node (ref "C18") (pin "2") (pinfunction "2_2") (pintype "passive"))
      (node (ref "C19") (pin "2") (pinfunction "2_2") (pintype "passive"))
      (node (ref "C2") (pin "1") (pinfunction "1_1") (pintype "passive"))
      (node (ref "C20") (pin "2") (pinfunction "2_2") (pintype "passive"))
      (node (ref "C24") (pin "2") (pinfunction "2_2") (pintype "passive"))
      (node (ref "C25") (pin "2") (pinfunction "2_2") (pintype "passive"))
      (node (ref "C26") (pin "2") (pinfunction "2_2") (pintype "passive"))
      (node (ref "C27") (pin "2") (pinfunction "2_2") (pintype "passive"))
      (node (ref "C28") (pin "2") (pinfunction "2_2") (pintype "passive"))
      (node (ref "C29") (pin "2") (pinfunction "2_2") (pintype "passive"))
      (node (ref "C30") (pin "1") (pinfunction "1_1") (pintype "passive"))
      (node (ref "C4") (pin "2") (pinfunction "2_2") (pintype "passive"))
      (node (ref "C7") (pin "1") (pinfunction "1_1") (pintype "passive"))
      (node (ref "C8") (pin "2") (pinfunction "2_2") (pintype "passive"))
      (node (ref "D1") (pin "2") (pinfunction "K_2") (pintype "passive"))
      (node (ref "P1") (pin "19") (pinfunction "19_19") (pintype "passive"))
      (node (ref "P1") (pin "20") (pinfunction "20_20") (pintype "passive"))
      (node (ref "P2") (pin "19") (pinfunction "19_19") (pintype "passive"))
      (node (ref "P2") (pin "20") (pinfunction "20_20") (pintype "passive"))
      (node (ref "Q4") (pin "2") (pinfunction "E_2") (pintype "passive"))
      (node (ref "R11") (pin "2") (pinfunction "2_2") (pintype "passive"))
      (node (ref "R22") (pin "2") (pinfunction "2_2") (pintype "passive"))
      (node (ref "R25") (pin "2") (pinfunction "2_2") (pintype "passive"))
      (node (ref "R32") (pin "1") (pinfunction "1_1") (pintype "passive"))
      (node (ref "R33") (pin "1") (pinfunction "1_1") (pintype "passive"))
      (node (ref "R39") (pin "2") (pinfunction "2_2") (pintype "passive"))
      (node (ref "R4") (pin "2") (pinfunction "2_2") (pintype "passive"))
      (node (ref "R41") (pin "3") (pinfunction "3_3") (pintype "passive"))
      (node (ref "R42") (pin "1") (pinfunction "1_1") (pintype "passive"))
      (node (ref "R8") (pin "2") (pinfunction "2_2") (pintype "passive"))
      (node (ref "SW1") (pin "2") (pinfunction "C_2") (pintype "passive"))
      (node (ref "SW2") (pin "2") (pinfunction "C_2") (pintype "passive"))
      (node (ref "U10") (pin "1") (pinfunction "GND_1") (pintype "passive"))
      (node (ref "U11") (pin "8") (pinfunction "E_8") (pintype "passive"))
      (node (ref "U12") (pin "6") (pinfunction "~{EN}_6") (pintype "passive"))
      (node (ref "U12") (pin "7") (pinfunction "VEE_7") (pintype "passive"))
      (node (ref "U12") (pin "8") (pinfunction "GND_8") (pintype "passive"))
      (node (ref "U13") (pin "7") (pinfunction "GND_7") (pintype "passive"))
      (node (ref "U14") (pin "7") (pinfunction "GND_7") (pintype "passive"))
      (node (ref "U15") (pin "7") (pinfunction "GND_7") (pintype "passive"))
      (node (ref "U16") (pin "13") (pinfunction "GND_13") (pintype "passive"))
      (node (ref "U16") (pin "16") (pinfunction "VREF-_16") (pintype "passive"))
      (node (ref "U16") (pin "23") (pinfunction "ADD_C_23") (pintype "passive"))
      (node (ref "U16") (pin "24") (pinfunction "ADD_B_24") (pintype "passive"))
      (node (ref "U2") (pin "1") (pinfunction "-_1") (pintype "passive"))
      (node (ref "U3") (pin "6") (pinfunction "~{EN}_6") (pintype "passive"))
      (node (ref "U3") (pin "7") (pinfunction "VEE_7") (pintype "passive"))
      (node (ref "U3") (pin "8") (pinfunction "GND_8") (pintype "passive"))
      (node (ref "U5") (pin "1") (pinfunction "GND_1") (pintype "passive"))
      (node (ref "U6") (pin "2") (pinfunction "GND_2") (pintype "passive"))
      (node (ref "U6") (pin "4") (pinfunction "GND_4") (pintype "passive"))
      (node (ref "U7") (pin "3") (pinfunction "P0_3") (pintype "passive"))
      (node (ref "U7") (pin "4") (pinfunction "P1_4") (pintype "passive"))
      (node (ref "U7") (pin "5") (pinfunction "P2_5") (pintype "passive"))
      (node (ref "U7") (pin "6") (pinfunction "P3_6") (pintype "passive"))
      (node (ref "U7") (pin "8") (pinfunction "GND_8") (pintype "passive"))
      (node (ref "U8") (pin "1") (pinfunction "GND_1") (pintype "passive"))
      (node (ref "U9") (pin "1") (pinfunction "-_1") (pintype "passive"))
    )
    (net (code "47") (name "Net-(*1-Vin1+)") (class "Default")
      (node (ref "*1") (pin "3") (pinfunction "Vin1+_3") (pintype "passive"))
      (node (ref "R21") (pin "2") (pinfunction "2_2") (pintype "passive"))
      (node (ref "R22") (pin "1") (pinfunction "1_1") (pintype "passive"))
    )
    (net (code "48") (name "Net-(*3-3.3V-Pad2)") (class "Default")
      (node (ref "*3") (pin "2") (pinfunction "3.3V_2") (pintype "passive"))
      (node (ref "P2") (pin "2") (pinfunction "2_2") (pintype "passive"))
    )
    (net (code "49") (name "Net-(*3-3.3V-Pad39)") (class "Default")
      (node (ref "*3") (pin "39") (pinfunction "3.3V_39") (pintype "passive"))
      (node (ref "P1") (pin "2") (pinfunction "2_2") (pintype "passive"))
    )
    (net (code "50") (name "Net-(*3-P3.0)") (class "Default")
      (node (ref "*3") (pin "30") (pinfunction "P3.0_30") (pintype "passive"))
      (node (ref "P1") (pin "11") (pinfunction "11_11") (pintype "passive"))
    )
    (net (code "51") (name "Net-(*4-LEDA)") (class "Default")
      (node (ref "*4") (pin "19") (pinfunction "LEDA_19") (pintype "passive"))
      (node (ref "R41") (pin "2") (pinfunction "2_2") (pintype "passive"))
    )
    (net (code "52") (name "Net-(*4-V0)") (class "Default")
      (node (ref "*4") (pin "5") (pinfunction "V0_5") (pintype "passive"))
      (node (ref "R42") (pin "2") (pinfunction "2_2") (pintype "passive"))
    )
    (net (code "53") (name "Net-(BUZZER1-+)") (class "Default")
      (node (ref "BUZZER1") (pin "1") (pinfunction "+_1") (pintype "passive"))
      (node (ref "R28") (pin "2") (pinfunction "2_2") (pintype "passive"))
    )
    (net (code "54") (name "Net-(C21-Pad1)") (class "Default")
      (node (ref "C21") (pin "1") (pinfunction "1_1") (pintype "passive"))
      (node (ref "C24") (pin "1") (pinfunction "1_1") (pintype "passive"))
      (node (ref "R34") (pin "2") (pinfunction "2_2") (pintype "passive"))
    )
    (net (code "55") (name "Net-(C21-Pad2)") (class "Default")
      (node (ref "C21") (pin "2") (pinfunction "2_2") (pintype "passive"))
      (node (ref "R33") (pin "2") (pinfunction "2_2") (pintype "passive"))
    )
    (net (code "56") (name "Net-(D1-A)") (class "Default")
      (node (ref "D1") (pin "1") (pinfunction "A_1") (pintype "passive"))
      (node (ref "R1") (pin "1") (pinfunction "1_1") (pintype "passive"))
    )
    (net (code "57") (name "Net-(D4-K)") (class "Default")
      (node (ref "C20") (pin "1") (pinfunction "1_1") (pintype "passive"))
      (node (ref "D4") (pin "1") (pinfunction "K_1") (pintype "passive"))
      (node (ref "Q3") (pin "3") (pinfunction "C_3") (pintype "passive"))
      (node (ref "R29") (pin "2") (pinfunction "2_2") (pintype "passive"))
      (node (ref "R30") (pin "1") (pinfunction "1_1") (pintype "passive"))
      (node (ref "R31") (pin "1") (pinfunction "1_1") (pintype "passive"))
      (node (ref "U10") (pin "4") (pinfunction "R_4") (pintype "passive"))
      (node (ref "U10") (pin "8") (pinfunction "VCC_8") (pintype "passive"))
    )
    (net (code "58") (name "Net-(Q3-B)") (class "Default")
      (node (ref "Q3") (pin "1") (pinfunction "B_1") (pintype "passive"))
      (node (ref "R31") (pin "2") (pinfunction "2_2") (pintype "passive"))
      (node (ref "U12") (pin "13") (pinfunction "X_13") (pintype "passive"))
    )
    (net (code "59") (name "Net-(Q3-E)") (class "Default")
      (node (ref "C22") (pin "1") (pinfunction "1_1") (pintype "passive"))
      (node (ref "Q3") (pin "2") (pinfunction "E_2") (pintype "passive"))
      (node (ref "R39") (pin "1") (pinfunction "1_1") (pintype "passive"))
    )
    (net (code "60") (name "Net-(Q4-B)") (class "Default")
      (node (ref "C23") (pin "1") (pinfunction "1_1") (pintype "passive"))
      (node (ref "Q4") (pin "1") (pinfunction "B_1") (pintype "passive"))
      (node (ref "R36") (pin "1") (pinfunction "1_1") (pintype "passive"))
      (node (ref "R37") (pin "2") (pinfunction "2_2") (pintype "passive"))
    )
    (net (code "61") (name "Net-(SW2-B)") (class "Default")
      (node (ref "R40") (pin "2") (pinfunction "2_2") (pintype "passive"))
      (node (ref "SW2") (pin "3") (pinfunction "B_3") (pintype "passive"))
      (node (ref "U13") (pin "2") (pinfunction "1D_2") (pintype "passive"))
    )
    (net (code "62") (name "Net-(U2-+)") (class "Default")
      (node (ref "C4") (pin "1") (pinfunction "1_1") (pintype "passive"))
      (node (ref "U1") (pin "2") (pinfunction "2_2") (pintype "passive"))
      (node (ref "U2") (pin "2") (pinfunction "+_2") (pintype "passive"))
    )
    (net (code "63") (name "Net-(U3-X0)") (class "Default")
      (node (ref "R11") (pin "1") (pinfunction "1_1") (pintype "passive"))
      (node (ref "U3") (pin "12") (pinfunction "X0_12") (pintype "passive"))
    )
    (net (code "64") (name "Net-(U3-X1)") (class "Default")
      (node (ref "R8") (pin "1") (pinfunction "1_1") (pintype "passive"))
      (node (ref "U3") (pin "14") (pinfunction "X1_14") (pintype "passive"))
    )
    (net (code "65") (name "Net-(U3-X2)") (class "Default")
      (node (ref "R4") (pin "1") (pinfunction "1_1") (pintype "passive"))
      (node (ref "U3") (pin "15") (pinfunction "X2_15") (pintype "passive"))
    )
    (net (code "66") (name "Net-(U3-Y0)") (class "Default")
      (node (ref "R2") (pin "2") (pinfunction "2_2") (pintype "passive"))
      (node (ref "U3") (pin "1") (pinfunction "Y0_1") (pintype "passive"))
    )
    (net (code "67") (name "Net-(U3-Y1)") (class "Default")
      (node (ref "R10") (pin "2") (pinfunction "2_2") (pintype "passive"))
      (node (ref "U3") (pin "5") (pinfunction "Y1_5") (pintype "passive"))
    )
    (net (code "68") (name "Net-(U3-Y2)") (class "Default")
      (node (ref "R3") (pin "2") (pinfunction "2_2") (pintype "passive"))
      (node (ref "U3") (pin "2") (pinfunction "Y2_2") (pintype "passive"))
    )
    (net (code "69") (name "Net-(U5-CONT)") (class "Default")
      (node (ref "C7") (pin "2") (pinfunction "2_2") (pintype "passive"))
      (node (ref "U5") (pin "5") (pinfunction "CONT_5") (pintype "passive"))
    )
    (net (code "70") (name "Net-(U5-DISCH)") (class "Default")
      (node (ref "R13") (pin "1") (pinfunction "1_1") (pintype "passive"))
      (node (ref "R9") (pin "1") (pinfunction "1_1") (pintype "passive"))
      (node (ref "U5") (pin "7") (pinfunction "DISCH_7") (pintype "passive"))
    )
    (net (code "71") (name "Net-(U5-THRES)") (class "Default")
      (node (ref "C8") (pin "1") (pinfunction "1_1") (pintype "passive"))
      (node (ref "R13") (pin "2") (pinfunction "2_2") (pintype "passive"))
      (node (ref "U5") (pin "2") (pinfunction "TRIG_2") (pintype "passive"))
      (node (ref "U5") (pin "6") (pinfunction "THRES_6") (pintype "passive"))
    )
    (net (code "72") (name "Net-(U8-CONT)") (class "Default")
      (node (ref "C17") (pin "2") (pinfunction "2_2") (pintype "passive"))
      (node (ref "U8") (pin "5") (pinfunction "CONT_5") (pintype "passive"))
    )
    (net (code "73") (name "Net-(U8-DISCH)") (class "Default")
      (node (ref "R17") (pin "1") (pinfunction "1_1") (pintype "passive"))
      (node (ref "R18") (pin "1") (pinfunction "1_1") (pintype "passive"))
      (node (ref "R20") (pin "1") (pinfunction "1_1") (pintype "passive"))
      (node (ref "U8") (pin "7") (pinfunction "DISCH_7") (pintype "passive"))
    )
    (net (code "74") (name "Net-(U8-THRES)") (class "Default")
      (node (ref "C18") (pin "1") (pinfunction "1_1") (pintype "passive"))
      (node (ref "R20") (pin "2") (pinfunction "2_2") (pintype "passive"))
      (node (ref "U8") (pin "2") (pinfunction "TRIG_2") (pintype "passive"))
      (node (ref "U8") (pin "6") (pinfunction "THRES_6") (pintype "passive"))
    )
    (net (code "75") (name "Net-(U9-+)") (class "Default")
      (node (ref "R24") (pin "1") (pinfunction "1_1") (pintype "passive"))
      (node (ref "U9") (pin "2") (pinfunction "+_2") (pintype "passive"))
    )
    (net (code "76") (name "Net-(U10-CV)") (class "Default")
      (node (ref "C28") (pin "1") (pinfunction "1_1") (pintype "passive"))
      (node (ref "U10") (pin "5") (pinfunction "CV_5") (pintype "passive"))
    )
    (net (code "77") (name "Net-(U10-DC)") (class "Default")
      (node (ref "R29") (pin "1") (pinfunction "1_1") (pintype "passive"))
      (node (ref "R38") (pin "3") (pinfunction "3_3") (pintype "passive"))
      (node (ref "U10") (pin "7") (pinfunction "DC_7") (pintype "passive"))
    )
    (net (code "78") (name "Net-(U10-Q)") (class "Default")
      (node (ref "R32") (pin "3") (pinfunction "3_3") (pintype "passive"))
      (node (ref "R33") (pin "3") (pinfunction "3_3") (pintype "passive"))
      (node (ref "U10") (pin "3") (pinfunction "Q_3") (pintype "passive"))
    )
    (net (code "79") (name "Net-(U10-TH)") (class "Default")
      (node (ref "C27") (pin "1") (pinfunction "1_1") (pintype "passive"))
      (node (ref "R38") (pin "1") (pinfunction "1_1") (pintype "passive"))
      (node (ref "R38") (pin "2") (pinfunction "2_2") (pintype "passive"))
      (node (ref "U10") (pin "2") (pinfunction "TR_2") (pintype "passive"))
      (node (ref "U10") (pin "6") (pinfunction "TH_6") (pintype "passive"))
    )
    (net (code "80") (name "Net-(U11-1C)") (class "Default")
      (node (ref "BUZZER1") (pin "2") (pinfunction "2_2") (pintype "passive"))
      (node (ref "U11") (pin "16") (pinfunction "1C_16") (pintype "passive"))
    )
    (net (code "81") (name "Net-(U13-1Q)") (class "Default")
      (node (ref "U13") (pin "12") (pinfunction "2D_12") (pintype "passive"))
      (node (ref "U13") (pin "5") (pinfunction "1Q_5") (pintype "passive"))
      (node (ref "U14") (pin "2") (pinfunction "1A_2") (pintype "passive"))
    )
    (net (code "82") (name "Net-(U13-2Q)") (class "Default")
      (node (ref "U13") (pin "9") (pinfunction "2Q_9") (pintype "passive"))
      (node (ref "U14") (pin "3") (pinfunction "1B_3") (pintype "passive"))
    )
    (net (code "83") (name "Net-(U14-1Y)") (class "Default")
      (node (ref "U14") (pin "1") (pinfunction "1Y_1") (pintype "passive"))
      (node (ref "U15") (pin "1") (pinfunction "1A_1") (pintype "passive"))
    )
    (net (code "84") (name "SIGNAL1") (class "Default")
      (node (ref "*2") (pin "3") (pinfunction "Vin1+_3") (pintype "passive"))
      (node (ref "R24") (pin "2") (pinfunction "2_2") (pintype "passive"))
      (node (ref "R25") (pin "1") (pinfunction "1_1") (pintype "passive"))
    )
    (net (code "85") (name "SIGNAL2") (class "Default")
      (node (ref "*2") (pin "1") (pinfunction "Vout1_1") (pintype "passive"))
      (node (ref "*2") (pin "2") (pinfunction "Vin1-_2") (pintype "passive"))
      (node (ref "R10") (pin "1") (pinfunction "1_1") (pintype "passive"))
      (node (ref "R2") (pin "1") (pinfunction "1_1") (pintype "passive"))
      (node (ref "R3") (pin "1") (pinfunction "1_1") (pintype "passive"))
    )
    (net (code "86") (name "WAV1") (class "Default")
      (node (ref "*2") (pin "7") (pinfunction "Vout2_7") (pintype "passive"))
      (node (ref "R26") (pin "2") (pinfunction "2_2") (pintype "passive"))
      (node (ref "U16") (pin "26") (pinfunction "IN0_26") (pintype "passive"))
    )
    (net (code "87") (name "WAV2") (class "Default")
      (node (ref "C22") (pin "2") (pinfunction "2_2") (pintype "passive"))
      (node (ref "U16") (pin "27") (pinfunction "IN1_27") (pintype "passive"))
    )
    (net (code "88") (name "unconnected-(*1-Vin2+-Pad5)") (class "Default")
      (node (ref "*1") (pin "5") (pinfunction "Vin2+_5") (pintype "passive"))
    )
    (net (code "89") (name "unconnected-(*1-Vin2--Pad6)") (class "Default")
      (node (ref "*1") (pin "6") (pinfunction "Vin2-_6") (pintype "passive"))
    )
    (net (code "90") (name "unconnected-(*1-Vout2-Pad7)") (class "Default")
      (node (ref "*1") (pin "7") (pinfunction "Vout2_7") (pintype "passive"))
    )
    (net (code "91") (name "unconnected-(SW1-A-Pad1)") (class "Default")
      (node (ref "SW1") (pin "1") (pinfunction "A_1") (pintype "passive"))
    )
    (net (code "92") (name "unconnected-(SW1-D-Pad4)") (class "Default")
      (node (ref "SW1") (pin "4") (pinfunction "D_4") (pintype "passive"))
    )
    (net (code "93") (name "unconnected-(SW2-A-Pad1)") (class "Default")
      (node (ref "SW2") (pin "1") (pinfunction "A_1") (pintype "passive"))
    )
    (net (code "94") (name "unconnected-(SW2-D-Pad4)") (class "Default")
      (node (ref "SW2") (pin "4") (pinfunction "D_4") (pintype "passive"))
    )
    (net (code "95") (name "unconnected-(U1-Pad1)") (class "Default")
      (node (ref "U1") (pin "1") (pinfunction "1_1") (pintype "passive+no_connect"))
    )
    (net (code "96") (name "unconnected-(U3-X3-Pad11)") (class "Default")
      (node (ref "U3") (pin "11") (pinfunction "X3_11") (pintype "passive+no_connect"))
    )
    (net (code "97") (name "unconnected-(U3-Y3-Pad4)") (class "Default")
      (node (ref "U3") (pin "4") (pinfunction "Y3_4") (pintype "passive+no_connect"))
    )
    (net (code "98") (name "unconnected-(U7-MR#-Pad1)") (class "Default")
      (node (ref "U7") (pin "1") (pinfunction "MR#_1") (pintype "passive"))
    )
    (net (code "99") (name "unconnected-(U7-Q2-Pad12)") (class "Default")
      (node (ref "U7") (pin "12") (pinfunction "Q2_12") (pintype "passive"))
    )
    (net (code "100") (name "unconnected-(U7-Q3-Pad11)") (class "Default")
      (node (ref "U7") (pin "11") (pinfunction "Q3_11") (pintype "passive"))
    )
    (net (code "101") (name "unconnected-(U7-TC-Pad15)") (class "Default")
      (node (ref "U7") (pin "15") (pinfunction "TC_15") (pintype "passive"))
    )
    (net (code "102") (name "unconnected-(U11-2B-Pad2)") (class "Default")
      (node (ref "U11") (pin "2") (pinfunction "2B_2") (pintype "passive"))
    )
    (net (code "103") (name "unconnected-(U11-2C-Pad15)") (class "Default")
      (node (ref "U11") (pin "15") (pinfunction "2C_15") (pintype "passive"))
    )
    (net (code "104") (name "unconnected-(U11-3B-Pad3)") (class "Default")
      (node (ref "U11") (pin "3") (pinfunction "3B_3") (pintype "passive"))
    )
    (net (code "105") (name "unconnected-(U11-3C-Pad14)") (class "Default")
      (node (ref "U11") (pin "14") (pinfunction "3C_14") (pintype "passive"))
    )
    (net (code "106") (name "unconnected-(U11-4B-Pad4)") (class "Default")
      (node (ref "U11") (pin "4") (pinfunction "4B_4") (pintype "passive"))
    )
    (net (code "107") (name "unconnected-(U11-4C-Pad13)") (class "Default")
      (node (ref "U11") (pin "13") (pinfunction "4C_13") (pintype "passive"))
    )
    (net (code "108") (name "unconnected-(U11-5B-Pad5)") (class "Default")
      (node (ref "U11") (pin "5") (pinfunction "5B_5") (pintype "passive"))
    )
    (net (code "109") (name "unconnected-(U11-5C-Pad12)") (class "Default")
      (node (ref "U11") (pin "12") (pinfunction "5C_12") (pintype "passive"))
    )
    (net (code "110") (name "unconnected-(U11-6B-Pad6)") (class "Default")
      (node (ref "U11") (pin "6") (pinfunction "6B_6") (pintype "passive"))
    )
    (net (code "111") (name "unconnected-(U11-6C-Pad11)") (class "Default")
      (node (ref "U11") (pin "11") (pinfunction "6C_11") (pintype "passive"))
    )
    (net (code "112") (name "unconnected-(U11-7B-Pad7)") (class "Default")
      (node (ref "U11") (pin "7") (pinfunction "7B_7") (pintype "passive"))
    )
    (net (code "113") (name "unconnected-(U11-7C-Pad10)") (class "Default")
      (node (ref "U11") (pin "10") (pinfunction "7C_10") (pintype "passive"))
    )
    (net (code "114") (name "unconnected-(U12-Y-Pad3)") (class "Default")
      (node (ref "U12") (pin "3") (pinfunction "Y_3") (pintype "passive+no_connect"))
    )
    (net (code "115") (name "unconnected-(U12-Y0-Pad1)") (class "Default")
      (node (ref "U12") (pin "1") (pinfunction "Y0_1") (pintype "passive+no_connect"))
    )
    (net (code "116") (name "unconnected-(U12-Y1-Pad5)") (class "Default")
      (node (ref "U12") (pin "5") (pinfunction "Y1_5") (pintype "passive+no_connect"))
    )
    (net (code "117") (name "unconnected-(U12-Y2-Pad2)") (class "Default")
      (node (ref "U12") (pin "2") (pinfunction "Y2_2") (pintype "passive+no_connect"))
    )
    (net (code "118") (name "unconnected-(U12-Y3-Pad4)") (class "Default")
      (node (ref "U12") (pin "4") (pinfunction "Y3_4") (pintype "passive+no_connect"))
    )
    (net (code "119") (name "unconnected-(U13-1CLR#-Pad1)") (class "Default")
      (node (ref "U13") (pin "1") (pinfunction "1CLR#_1") (pintype "passive"))
    )
    (net (code "120") (name "unconnected-(U13-1PRE#-Pad4)") (class "Default")
      (node (ref "U13") (pin "4") (pinfunction "1PRE#_4") (pintype "passive"))
    )
    (net (code "121") (name "unconnected-(U13-1Q#-Pad6)") (class "Default")
      (node (ref "U13") (pin "6") (pinfunction "1Q#_6") (pintype "passive"))
    )
    (net (code "122") (name "unconnected-(U13-2CLR#-Pad13)") (class "Default")
      (node (ref "U13") (pin "13") (pinfunction "2CLR#_13") (pintype "passive"))
    )
    (net (code "123") (name "unconnected-(U13-2PRE#-Pad10)") (class "Default")
      (node (ref "U13") (pin "10") (pinfunction "2PRE#_10") (pintype "passive"))
    )
    (net (code "124") (name "unconnected-(U13-2Q#-Pad8)") (class "Default")
      (node (ref "U13") (pin "8") (pinfunction "2Q#_8") (pintype "passive"))
    )
    (net (code "125") (name "unconnected-(U14-2A-Pad5)") (class "Default")
      (node (ref "U14") (pin "5") (pinfunction "2A_5") (pintype "passive"))
    )
    (net (code "126") (name "unconnected-(U14-2B-Pad6)") (class "Default")
      (node (ref "U14") (pin "6") (pinfunction "2B_6") (pintype "passive"))
    )
    (net (code "127") (name "unconnected-(U14-2Y-Pad4)") (class "Default")
      (node (ref "U14") (pin "4") (pinfunction "2Y_4") (pintype "passive"))
    )
    (net (code "128") (name "unconnected-(U14-3A-Pad8)") (class "Default")
      (node (ref "U14") (pin "8") (pinfunction "3A_8") (pintype "passive"))
    )
    (net (code "129") (name "unconnected-(U14-3B-Pad9)") (class "Default")
      (node (ref "U14") (pin "9") (pinfunction "3B_9") (pintype "passive"))
    )
    (net (code "130") (name "unconnected-(U14-3Y-Pad10)") (class "Default")
      (node (ref "U14") (pin "10") (pinfunction "3Y_10") (pintype "passive"))
    )
    (net (code "131") (name "unconnected-(U14-4A-Pad11)") (class "Default")
      (node (ref "U14") (pin "11") (pinfunction "4A_11") (pintype "passive"))
    )
    (net (code "132") (name "unconnected-(U14-4B-Pad12)") (class "Default")
      (node (ref "U14") (pin "12") (pinfunction "4B_12") (pintype "passive"))
    )
    (net (code "133") (name "unconnected-(U14-4Y-Pad13)") (class "Default")
      (node (ref "U14") (pin "13") (pinfunction "4Y_13") (pintype "passive"))
    )
    (net (code "134") (name "unconnected-(U15-2A-Pad3)") (class "Default")
      (node (ref "U15") (pin "3") (pinfunction "2A_3") (pintype "passive"))
    )
    (net (code "135") (name "unconnected-(U15-2Y-Pad4)") (class "Default")
      (node (ref "U15") (pin "4") (pinfunction "2Y_4") (pintype "passive"))
    )
    (net (code "136") (name "unconnected-(U15-3A-Pad5)") (class "Default")
      (node (ref "U15") (pin "5") (pinfunction "3A_5") (pintype "passive"))
    )
    (net (code "137") (name "unconnected-(U15-3Y-Pad6)") (class "Default")
      (node (ref "U15") (pin "6") (pinfunction "3Y_6") (pintype "passive"))
    )
    (net (code "138") (name "unconnected-(U15-4A-Pad9)") (class "Default")
      (node (ref "U15") (pin "9") (pinfunction "4A_9") (pintype "passive"))
    )
    (net (code "139") (name "unconnected-(U15-4Y-Pad8)") (class "Default")
      (node (ref "U15") (pin "8") (pinfunction "4Y_8") (pintype "passive"))
    )
    (net (code "140") (name "unconnected-(U15-6A-Pad13)") (class "Default")
      (node (ref "U15") (pin "13") (pinfunction "6A_13") (pintype "passive"))
    )
    (net (code "141") (name "unconnected-(U15-6Y-Pad12)") (class "Default")
      (node (ref "U15") (pin "12") (pinfunction "6Y_12") (pintype "passive"))
    )
    (net (code "142") (name "unconnected-(U16-IN2-Pad28)") (class "Default")
      (node (ref "U16") (pin "28") (pinfunction "IN2_28") (pintype "passive+no_connect"))
    )
    (net (code "143") (name "unconnected-(U16-IN3-Pad1)") (class "Default")
      (node (ref "U16") (pin "1") (pinfunction "IN3_1") (pintype "passive+no_connect"))
    )
    (net (code "144") (name "unconnected-(U16-IN4-Pad2)") (class "Default")
      (node (ref "U16") (pin "2") (pinfunction "IN4_2") (pintype "passive+no_connect"))
    )
    (net (code "145") (name "unconnected-(U16-IN5-Pad3)") (class "Default")
      (node (ref "U16") (pin "3") (pinfunction "IN5_3") (pintype "passive+no_connect"))
    )
    (net (code "146") (name "unconnected-(U16-IN6-Pad4)") (class "Default")
      (node (ref "U16") (pin "4") (pinfunction "IN6_4") (pintype "passive+no_connect"))
    )
    (net (code "147") (name "unconnected-(U16-IN7-Pad5)") (class "Default")
      (node (ref "U16") (pin "5") (pinfunction "IN7_5") (pintype "passive+no_connect"))
    )
  )
)
